# Power.net
KiCad netlist of a schematic drawn in Altium Designer
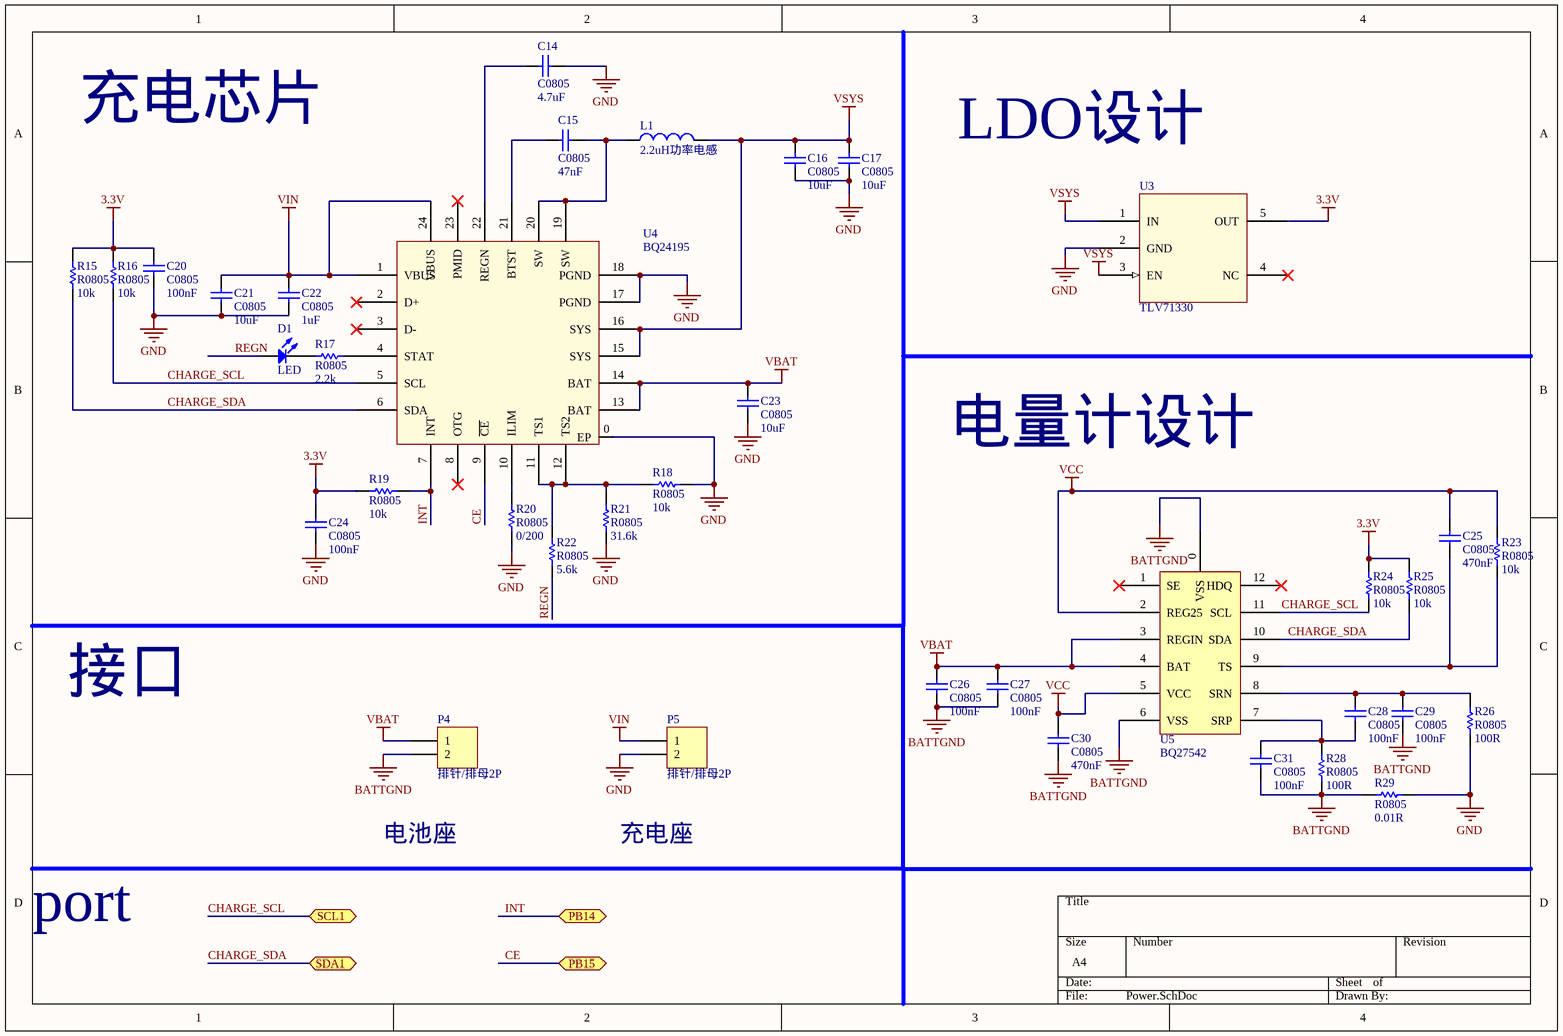
[diagram p0: Power.SchDoc]

(export (version "E")
  (design (tool "Eeschema 10.0.6"))
  (components
    (comp (ref "C14")
      (value "4.7uF")
      (footprint "C0805_200X125X140L50N")
      (description "0805 SMT MLCC Capacitor")
      (fields
        (field (name "VOLTAGE") "50V")
        (field (name "TOLERANCE") "10%")
        (field (name "CASE/PACKAGE") "C0805")
        (field (name "PUBLISHER") "Altium Limited")
      )
      (libsource (lib "ayaya0lib") (part "Cap0805"))
    )
    (comp (ref "C15")
      (value "47nF")
      (footprint "C0805_200X125X140L50N")
      (description "0805 SMT MLCC Capacitor")
      (fields
        (field (name "VOLTAGE") "50V")
        (field (name "TOLERANCE") "10%")
        (field (name "CASE/PACKAGE") "C0805")
        (field (name "PUBLISHER") "Altium Limited")
      )
      (libsource (lib "ayaya0lib") (part "Cap0805"))
    )
    (comp (ref "C16")
      (value "10uF")
      (footprint "C0805_200X125X140L50N")
      (description "0805 SMT MLCC Capacitor")
      (fields
        (field (name "VOLTAGE") "50V")
        (field (name "TOLERANCE") "10%")
        (field (name "CASE/PACKAGE") "C0805")
        (field (name "PUBLISHER") "Altium Limited")
      )
      (libsource (lib "ayaya0lib") (part "Cap0805"))
    )
    (comp (ref "C17")
      (value "10uF")
      (footprint "C0805_200X125X140L50N")
      (description "0805 SMT MLCC Capacitor")
      (fields
        (field (name "VOLTAGE") "50V")
        (field (name "TOLERANCE") "10%")
        (field (name "CASE/PACKAGE") "C0805")
        (field (name "PUBLISHER") "Altium Limited")
      )
      (libsource (lib "ayaya0lib") (part "Cap0805"))
    )
    (comp (ref "C20")
      (value "100nF")
      (footprint "C0805_200X125X140L50N")
      (description "0805 SMT MLCC Capacitor")
      (fields
        (field (name "VOLTAGE") "50V")
        (field (name "TOLERANCE") "10%")
        (field (name "CASE/PACKAGE") "C0805")
        (field (name "PUBLISHER") "Altium Limited")
      )
      (libsource (lib "ayaya0lib") (part "Cap0805"))
    )
    (comp (ref "C21")
      (value "10uF")
      (footprint "C0805_200X125X140L50N")
      (description "0805 SMT MLCC Capacitor")
      (fields
        (field (name "VOLTAGE") "50V")
        (field (name "TOLERANCE") "10%")
        (field (name "CASE/PACKAGE") "C0805")
        (field (name "PUBLISHER") "Altium Limited")
      )
      (libsource (lib "ayaya0lib") (part "Cap0805"))
    )
    (comp (ref "C22")
      (value "1uF")
      (footprint "C0805_200X125X140L50N")
      (description "0805 SMT MLCC Capacitor")
      (fields
        (field (name "VOLTAGE") "50V")
        (field (name "TOLERANCE") "10%")
        (field (name "CASE/PACKAGE") "C0805")
        (field (name "PUBLISHER") "Altium Limited")
      )
      (libsource (lib "ayaya0lib") (part "Cap0805"))
    )
    (comp (ref "C23")
      (value "10uF")
      (footprint "C0805_200X125X140L50N")
      (description "0805 SMT MLCC Capacitor")
      (fields
        (field (name "VOLTAGE") "50V")
        (field (name "TOLERANCE") "10%")
        (field (name "CASE/PACKAGE") "C0805")
        (field (name "PUBLISHER") "Altium Limited")
      )
      (libsource (lib "ayaya0lib") (part "Cap0805"))
    )
    (comp (ref "C24")
      (value "100nF")
      (footprint "C0805_200X125X140L50N")
      (description "0805 SMT MLCC Capacitor")
      (fields
        (field (name "VOLTAGE") "50V")
        (field (name "TOLERANCE") "10%")
        (field (name "CASE/PACKAGE") "C0805")
        (field (name "PUBLISHER") "Altium Limited")
      )
      (libsource (lib "ayaya0lib") (part "Cap0805"))
    )
    (comp (ref "C25")
      (value "470nF")
      (footprint "C0805_200X125X140L50N")
      (description "0805 SMT MLCC Capacitor")
      (fields
        (field (name "VOLTAGE") "50V")
        (field (name "TOLERANCE") "10%")
        (field (name "CASE/PACKAGE") "C0805")
        (field (name "PUBLISHER") "Altium Limited")
      )
      (libsource (lib "ayaya0lib") (part "Cap0805"))
    )
    (comp (ref "C26")
      (value "100nF")
      (footprint "C0805_200X125X140L50N")
      (description "0805 SMT MLCC Capacitor")
      (fields
        (field (name "VOLTAGE") "50V")
        (field (name "TOLERANCE") "10%")
        (field (name "CASE/PACKAGE") "C0805")
        (field (name "PUBLISHER") "Altium Limited")
      )
      (libsource (lib "ayaya0lib") (part "Cap0805"))
    )
    (comp (ref "C27")
      (value "100nF")
      (footprint "C0805_200X125X140L50N")
      (description "0805 SMT MLCC Capacitor")
      (fields
        (field (name "VOLTAGE") "50V")
        (field (name "TOLERANCE") "10%")
        (field (name "CASE/PACKAGE") "C0805")
        (field (name "PUBLISHER") "Altium Limited")
      )
      (libsource (lib "ayaya0lib") (part "Cap0805"))
    )
    (comp (ref "C28")
      (value "100nF")
      (footprint "C0805_200X125X140L50N")
      (description "0805 SMT MLCC Capacitor")
      (fields
        (field (name "VOLTAGE") "50V")
        (field (name "TOLERANCE") "10%")
        (field (name "CASE/PACKAGE") "C0805")
        (field (name "PUBLISHER") "Altium Limited")
      )
      (libsource (lib "ayaya0lib") (part "Cap0805"))
    )
    (comp (ref "C29")
      (value "100nF")
      (footprint "C0805_200X125X140L50N")
      (description "0805 SMT MLCC Capacitor")
      (fields
        (field (name "VOLTAGE") "50V")
        (field (name "TOLERANCE") "10%")
        (field (name "CASE/PACKAGE") "C0805")
        (field (name "PUBLISHER") "Altium Limited")
      )
      (libsource (lib "ayaya0lib") (part "Cap0805"))
    )
    (comp (ref "C30")
      (value "470nF")
      (footprint "C0805_200X125X140L50N")
      (description "0805 SMT MLCC Capacitor")
      (fields
        (field (name "VOLTAGE") "50V")
        (field (name "TOLERANCE") "10%")
        (field (name "CASE/PACKAGE") "C0805")
        (field (name "PUBLISHER") "Altium Limited")
      )
      (libsource (lib "ayaya0lib") (part "Cap0805"))
    )
    (comp (ref "C31")
      (value "100nF")
      (footprint "C0805_200X125X140L50N")
      (description "0805 SMT MLCC Capacitor")
      (fields
        (field (name "VOLTAGE") "50V")
        (field (name "TOLERANCE") "10%")
        (field (name "CASE/PACKAGE") "C0805")
        (field (name "PUBLISHER") "Altium Limited")
      )
      (libsource (lib "ayaya0lib") (part "Cap0805"))
    )
    (comp (ref "D1")
      (value "LED")
      (footprint "LED0805")
      (description "Typical RED, GREEN, YELLOW, AMBER GaAs LED")
      (fields (field (name "PUBLISHER") "Altium Limited"))
      (libsource (lib "earth_ed") (part "LED"))
    )
    (comp (ref "L1")
      (value "2.2uH功率电感4NR4018T2R2M")
      (footprint "4018")
      (description "电感")
      (fields (field (name "ALTIUM_UNNAMED_1") "2.2uH功率电感") (field (name "创建") "高鹏20160422"))
      (libsource (lib "earth_ed") (part "L"))
    )
    (comp (ref "P4")
      (value "排针/排母2P")
      (footprint "HDR1X2")
      (description "Header, 2-Pin")
      (fields (field (name "PUBLISHER") "Altium Limited"))
      (libsource (lib "earth_ed") (part "Header 2"))
    )
    (comp (ref "P5")
      (value "排针/排母2P")
      (footprint "HDR1X2")
      (description "Header, 2-Pin")
      (fields (field (name "PUBLISHER") "Altium Limited"))
      (libsource (lib "earth_ed") (part "Header 2"))
    )
    (comp (ref "R15")
      (value "10k")
      (footprint "R0805_200X125X140L50N")
      (description "0805 SMT Resistor")
      (fields
        (field (name "TOLERANCE") "1%")
        (field (name "CASE/PACKAGE") "R0805")
        (field (name "PUBLISHER") "Altium Limited")
      )
      (libsource (lib "ayaya0lib") (part "Res0805"))
    )
    (comp (ref "R16")
      (value "10k")
      (footprint "R0805_200X125X140L50N")
      (description "0805 SMT Resistor")
      (fields
        (field (name "TOLERANCE") "1%")
        (field (name "CASE/PACKAGE") "R0805")
        (field (name "PUBLISHER") "Altium Limited")
      )
      (libsource (lib "ayaya0lib") (part "Res0805"))
    )
    (comp (ref "R17")
      (value "2.2k")
      (footprint "R0805_200X125X140L50N")
      (description "0805 SMT Resistor")
      (fields
        (field (name "TOLERANCE") "1%")
        (field (name "CASE/PACKAGE") "R0805")
        (field (name "PUBLISHER") "Altium Limited")
      )
      (libsource (lib "ayaya0lib") (part "Res0805"))
    )
    (comp (ref "R18")
      (value "10k")
      (footprint "R0805_200X125X140L50N")
      (description "0805 SMT Resistor")
      (fields
        (field (name "TOLERANCE") "1%")
        (field (name "CASE/PACKAGE") "R0805")
        (field (name "PUBLISHER") "Altium Limited")
      )
      (libsource (lib "ayaya0lib") (part "Res0805"))
    )
    (comp (ref "R19")
      (value "10k")
      (footprint "R0805_200X125X140L50N")
      (description "0805 SMT Resistor")
      (fields
        (field (name "TOLERANCE") "1%")
        (field (name "CASE/PACKAGE") "R0805")
        (field (name "PUBLISHER") "Altium Limited")
      )
      (libsource (lib "ayaya0lib") (part "Res0805"))
    )
    (comp (ref "R20")
      (value "0/200")
      (footprint "R0805_200X125X140L50N")
      (description "0805 SMT Resistor")
      (fields
        (field (name "TOLERANCE") "1%")
        (field (name "CASE/PACKAGE") "R0805")
        (field (name "PUBLISHER") "Altium Limited")
      )
      (libsource (lib "ayaya0lib") (part "Res0805"))
    )
    (comp (ref "R21")
      (value "31.6k")
      (footprint "R0805_200X125X140L50N")
      (description "0805 SMT Resistor")
      (fields
        (field (name "TOLERANCE") "1%")
        (field (name "CASE/PACKAGE") "R0805")
        (field (name "PUBLISHER") "Altium Limited")
      )
      (libsource (lib "ayaya0lib") (part "Res0805"))
    )
    (comp (ref "R22")
      (value "5.6k")
      (footprint "R0805_200X125X140L50N")
      (description "0805 SMT Resistor")
      (fields
        (field (name "TOLERANCE") "1%")
        (field (name "CASE/PACKAGE") "R0805")
        (field (name "PUBLISHER") "Altium Limited")
      )
      (libsource (lib "ayaya0lib") (part "Res0805"))
    )
    (comp (ref "R23")
      (value "10k")
      (footprint "R0805_200X125X140L50N")
      (description "0805 SMT Resistor")
      (fields
        (field (name "TOLERANCE") "1%")
        (field (name "CASE/PACKAGE") "R0805")
        (field (name "PUBLISHER") "Altium Limited")
      )
      (libsource (lib "ayaya0lib") (part "Res0805"))
    )
    (comp (ref "R24")
      (value "10k")
      (footprint "R0805_200X125X140L50N")
      (description "0805 SMT Resistor")
      (fields
        (field (name "TOLERANCE") "1%")
        (field (name "CASE/PACKAGE") "R0805")
        (field (name "PUBLISHER") "Altium Limited")
      )
      (libsource (lib "ayaya0lib") (part "Res0805"))
    )
    (comp (ref "R25")
      (value "10k")
      (footprint "R0805_200X125X140L50N")
      (description "0805 SMT Resistor")
      (fields
        (field (name "TOLERANCE") "1%")
        (field (name "CASE/PACKAGE") "R0805")
        (field (name "PUBLISHER") "Altium Limited")
      )
      (libsource (lib "ayaya0lib") (part "Res0805"))
    )
    (comp (ref "R26")
      (value "100R")
      (footprint "R0805_200X125X140L50N")
      (description "0805 SMT Resistor")
      (fields
        (field (name "TOLERANCE") "1%")
        (field (name "CASE/PACKAGE") "R0805")
        (field (name "PUBLISHER") "Altium Limited")
      )
      (libsource (lib "ayaya0lib") (part "Res0805"))
    )
    (comp (ref "R28")
      (value "100R")
      (footprint "R0805_200X125X140L50N")
      (description "0805 SMT Resistor")
      (fields
        (field (name "TOLERANCE") "1%")
        (field (name "CASE/PACKAGE") "R0805")
        (field (name "PUBLISHER") "Altium Limited")
      )
      (libsource (lib "ayaya0lib") (part "Res0805"))
    )
    (comp (ref "R29")
      (value "0.01R")
      (footprint "R0805_200X125X140L50N")
      (description "0805 SMT Resistor")
      (fields
        (field (name "TOLERANCE") "1%")
        (field (name "CASE/PACKAGE") "R0805")
        (field (name "PUBLISHER") "Altium Limited")
      )
      (libsource (lib "ayaya0lib") (part "Res0805"))
    )
    (comp (ref "U3")
      (value "TLV71330")
      (footprint "SOT-23-5")
      (fields (field (name "MANUFACTURER") "Analog Devices"))
      (libsource (lib "earth_ed") (part "TLV71330"))
    )
    (comp (ref "U4")
      (value "BQ24195")
      (footprint "BQ24195 PVQFN42")
      (fields (field (name "MANUFACTURER") "TI"))
      (libsource (lib "earth_ed") (part "BQ24195"))
    )
    (comp (ref "U5")
      (value "BQ27542")
      (footprint "BQ27542-G1")
      (description "Single Cell Li-Ion Battery Fuel Gauge for Battery Pack Integration")
      (fields (field (name "MANUFACTURER") "TI"))
      (libsource (lib "earth_ed") (part "BQ27542"))
    )
  )
  (nets
    (net (code "1") (name "/CE") (class "Default")
      (node (ref "U4") (pin "9") (pinfunction "~{CE}_9") (pintype "passive"))
    )
    (net (code "2") (name "/CHARGE_SCL") (class "Default")
      (node (ref "R16") (pin "1") (pinfunction "1_1") (pintype "passive"))
      (node (ref "R24") (pin "1") (pinfunction "1_1") (pintype "passive"))
      (node (ref "U4") (pin "5") (pinfunction "SCL_5") (pintype "passive"))
      (node (ref "U5") (pin "11") (pinfunction "SCL_11") (pintype "passive"))
    )
    (net (code "3") (name "/CHARGE_SDA") (class "Default")
      (node (ref "R15") (pin "1") (pinfunction "1_1") (pintype "passive"))
      (node (ref "R25") (pin "1") (pinfunction "1_1") (pintype "passive"))
      (node (ref "U4") (pin "6") (pinfunction "SDA_6") (pintype "passive"))
      (node (ref "U5") (pin "10") (pinfunction "SDA_10") (pintype "passive"))
    )
    (net (code "4") (name "/INT") (class "Default")
      (node (ref "R19") (pin "1") (pinfunction "1_1") (pintype "passive"))
      (node (ref "U4") (pin "7") (pinfunction "INT_7") (pintype "passive"))
    )
    (net (code "5") (name "/REGN") (class "Default")
      (node (ref "D1") (pin "1") (pinfunction "A_1") (pintype "passive"))
      (node (ref "R22") (pin "2") (pinfunction "2_2") (pintype "passive"))
    )
    (net (code "6") (name "3.3V") (class "Default")
      (node (ref "C20") (pin "2") (pinfunction "2_2") (pintype "passive"))
      (node (ref "C24") (pin "2") (pinfunction "2_2") (pintype "passive"))
      (node (ref "R15") (pin "2") (pinfunction "2_2") (pintype "passive"))
      (node (ref "R16") (pin "2") (pinfunction "2_2") (pintype "passive"))
      (node (ref "R19") (pin "2") (pinfunction "2_2") (pintype "passive"))
      (node (ref "R24") (pin "2") (pinfunction "2_2") (pintype "passive"))
      (node (ref "R25") (pin "2") (pinfunction "2_2") (pintype "passive"))
      (node (ref "U3") (pin "5") (pinfunction "OUT_5") (pintype "power_in"))
    )
    (net (code "7") (name "BATTGND") (class "Default")
      (node (ref "C26") (pin "1") (pinfunction "1_1") (pintype "passive"))
      (node (ref "C27") (pin "1") (pinfunction "1_1") (pintype "passive"))
      (node (ref "C29") (pin "1") (pinfunction "1_1") (pintype "passive"))
      (node (ref "C30") (pin "1") (pinfunction "1_1") (pintype "passive"))
      (node (ref "C31") (pin "1") (pinfunction "1_1") (pintype "passive"))
      (node (ref "P4") (pin "2") (pinfunction "2_2") (pintype "passive"))
      (node (ref "R28") (pin "1") (pinfunction "1_1") (pintype "passive"))
      (node (ref "R29") (pin "2") (pinfunction "2_2") (pintype "passive"))
      (node (ref "U5") (pin "0") (pinfunction "VSS_0") (pintype "passive"))
      (node (ref "U5") (pin "6") (pinfunction "VSS_6") (pintype "passive"))
    )
    (net (code "8") (name "GND") (class "Default")
      (node (ref "C14") (pin "1") (pinfunction "1_1") (pintype "passive"))
      (node (ref "C16") (pin "1") (pinfunction "1_1") (pintype "passive"))
      (node (ref "C17") (pin "1") (pinfunction "1_1") (pintype "passive"))
      (node (ref "C20") (pin "1") (pinfunction "1_1") (pintype "passive"))
      (node (ref "C21") (pin "1") (pinfunction "1_1") (pintype "passive"))
      (node (ref "C22") (pin "1") (pinfunction "1_1") (pintype "passive"))
      (node (ref "C23") (pin "1") (pinfunction "1_1") (pintype "passive"))
      (node (ref "C24") (pin "1") (pinfunction "1_1") (pintype "passive"))
      (node (ref "P5") (pin "2") (pinfunction "2_2") (pintype "passive"))
      (node (ref "R18") (pin "2") (pinfunction "2_2") (pintype "passive"))
      (node (ref "R20") (pin "2") (pinfunction "2_2") (pintype "passive"))
      (node (ref "R21") (pin "2") (pinfunction "2_2") (pintype "passive"))
      (node (ref "R26") (pin "1") (pinfunction "1_1") (pintype "passive"))
      (node (ref "R29") (pin "1") (pinfunction "1_1") (pintype "passive"))
      (node (ref "U3") (pin "2") (pinfunction "GND_2") (pintype "passive"))
      (node (ref "U4") (pin "0") (pinfunction "EP_0") (pintype "passive"))
      (node (ref "U4") (pin "17") (pinfunction "PGND_17") (pintype "passive"))
      (node (ref "U4") (pin "18") (pinfunction "PGND_18") (pintype "passive"))
    )
    (net (code "9") (name "Net-(C15-Pad1)") (class "Default")
      (node (ref "C15") (pin "1") (pinfunction "1_1") (pintype "passive"))
      (node (ref "L1") (pin "1") (pinfunction "1_1") (pintype "passive"))
      (node (ref "U4") (pin "19") (pinfunction "SW_19") (pintype "passive"))
      (node (ref "U4") (pin "20") (pinfunction "SW_20") (pintype "passive"))
    )
    (net (code "10") (name "Net-(D1-K)") (class "Default")
      (node (ref "D1") (pin "2") (pinfunction "K_2") (pintype "passive"))
      (node (ref "R17") (pin "1") (pinfunction "1_1") (pintype "passive"))
    )
    (net (code "11") (name "Net-(U4-BTST)") (class "Default")
      (node (ref "C15") (pin "2") (pinfunction "2_2") (pintype "passive"))
      (node (ref "U4") (pin "21") (pinfunction "BTST_21") (pintype "power_in"))
    )
    (net (code "12") (name "Net-(U4-ILIM)") (class "Default")
      (node (ref "R20") (pin "1") (pinfunction "1_1") (pintype "passive"))
      (node (ref "U4") (pin "10") (pinfunction "ILIM_10") (pintype "passive"))
    )
    (net (code "13") (name "Net-(U4-REGN)") (class "Default")
      (node (ref "C14") (pin "2") (pinfunction "2_2") (pintype "passive"))
      (node (ref "U4") (pin "22") (pinfunction "REGN_22") (pintype "power_in"))
    )
    (net (code "14") (name "Net-(U4-STAT)") (class "Default")
      (node (ref "R17") (pin "2") (pinfunction "2_2") (pintype "passive"))
      (node (ref "U4") (pin "4") (pinfunction "STAT_4") (pintype "passive"))
    )
    (net (code "15") (name "Net-(U4-TS1)") (class "Default")
      (node (ref "R18") (pin "1") (pinfunction "1_1") (pintype "passive"))
      (node (ref "R21") (pin "1") (pinfunction "1_1") (pintype "passive"))
      (node (ref "R22") (pin "1") (pinfunction "1_1") (pintype "passive"))
      (node (ref "U4") (pin "11") (pinfunction "TS1_11") (pintype "passive"))
      (node (ref "U4") (pin "12") (pinfunction "TS2_12") (pintype "passive"))
    )
    (net (code "16") (name "Net-(U5-SRN)") (class "Default")
      (node (ref "C28") (pin "2") (pinfunction "2_2") (pintype "passive"))
      (node (ref "C29") (pin "2") (pinfunction "2_2") (pintype "passive"))
      (node (ref "R26") (pin "2") (pinfunction "2_2") (pintype "passive"))
      (node (ref "U5") (pin "8") (pinfunction "SRN_8") (pintype "passive"))
    )
    (net (code "17") (name "Net-(U5-SRP)") (class "Default")
      (node (ref "C28") (pin "1") (pinfunction "1_1") (pintype "passive"))
      (node (ref "C31") (pin "2") (pinfunction "2_2") (pintype "passive"))
      (node (ref "R28") (pin "2") (pinfunction "2_2") (pintype "passive"))
      (node (ref "U5") (pin "7") (pinfunction "SRP_7") (pintype "passive"))
    )
    (net (code "18") (name "Net-(U5-TS)") (class "Default")
      (node (ref "C25") (pin "1") (pinfunction "1_1") (pintype "passive"))
      (node (ref "R23") (pin "1") (pinfunction "1_1") (pintype "passive"))
      (node (ref "U5") (pin "9") (pinfunction "TS_9") (pintype "passive"))
    )
    (net (code "19") (name "VBAT") (class "Default")
      (node (ref "C23") (pin "2") (pinfunction "2_2") (pintype "passive"))
      (node (ref "C26") (pin "2") (pinfunction "2_2") (pintype "passive"))
      (node (ref "C27") (pin "2") (pinfunction "2_2") (pintype "passive"))
      (node (ref "P4") (pin "1") (pinfunction "1_1") (pintype "passive"))
      (node (ref "U4") (pin "13") (pinfunction "BAT_13") (pintype "power_in"))
      (node (ref "U4") (pin "14") (pinfunction "BAT_14") (pintype "power_in"))
      (node (ref "U5") (pin "3") (pinfunction "REGIN_3") (pintype "passive"))
      (node (ref "U5") (pin "4") (pinfunction "BAT_4") (pintype "passive"))
    )
    (net (code "20") (name "VCC") (class "Default")
      (node (ref "C25") (pin "2") (pinfunction "2_2") (pintype "passive"))
      (node (ref "C30") (pin "2") (pinfunction "2_2") (pintype "passive"))
      (node (ref "R23") (pin "2") (pinfunction "2_2") (pintype "passive"))
      (node (ref "U5") (pin "2") (pinfunction "REG25_2") (pintype "passive"))
      (node (ref "U5") (pin "5") (pinfunction "VCC_5") (pintype "passive"))
    )
    (net (code "21") (name "VIN") (class "Default")
      (node (ref "C21") (pin "2") (pinfunction "2_2") (pintype "passive"))
      (node (ref "C22") (pin "2") (pinfunction "2_2") (pintype "passive"))
      (node (ref "P5") (pin "1") (pinfunction "1_1") (pintype "passive"))
      (node (ref "U4") (pin "1") (pinfunction "VBUS_1") (pintype "power_in"))
      (node (ref "U4") (pin "24") (pinfunction "VBUS_24") (pintype "power_in"))
    )
    (net (code "22") (name "VSYS") (class "Default")
      (node (ref "C16") (pin "2") (pinfunction "2_2") (pintype "passive"))
      (node (ref "C17") (pin "2") (pinfunction "2_2") (pintype "passive"))
      (node (ref "L1") (pin "2") (pinfunction "2_2") (pintype "passive"))
      (node (ref "U3") (pin "1") (pinfunction "IN_1") (pintype "power_in"))
      (node (ref "U3") (pin "3") (pinfunction "EN_3") (pintype "input"))
      (node (ref "U4") (pin "15") (pinfunction "SYS_15") (pintype "power_in"))
      (node (ref "U4") (pin "16") (pinfunction "SYS_16") (pintype "power_in"))
    )
    (net (code "23") (name "unconnected-(U3-NC-Pad4)") (class "Default")
      (node (ref "U3") (pin "4") (pinfunction "NC_4") (pintype "passive+no_connect"))
    )
    (net (code "24") (name "unconnected-(U4-D+-Pad2)") (class "Default")
      (node (ref "U4") (pin "2") (pinfunction "D+_2") (pintype "passive+no_connect"))
    )
    (net (code "25") (name "unconnected-(U4-D--Pad3)") (class "Default")
      (node (ref "U4") (pin "3") (pinfunction "D-_3") (pintype "passive+no_connect"))
    )
    (net (code "26") (name "unconnected-(U4-OTG-Pad8)") (class "Default")
      (node (ref "U4") (pin "8") (pinfunction "OTG_8") (pintype "passive+no_connect"))
    )
    (net (code "27") (name "unconnected-(U4-PMID-Pad23)") (class "Default")
      (node (ref "U4") (pin "23") (pinfunction "PMID_23") (pintype "power_in+no_connect"))
    )
    (net (code "28") (name "unconnected-(U5-HDQ-Pad12)") (class "Default")
      (node (ref "U5") (pin "12") (pinfunction "HDQ_12") (pintype "passive+no_connect"))
    )
    (net (code "29") (name "unconnected-(U5-SE-Pad1)") (class "Default")
      (node (ref "U5") (pin "1") (pinfunction "SE_1") (pintype "passive+no_connect"))
    )
  )
)
